# rapidshark-dart-detector-backlight-mk-2_.net
KiCad netlist of a schematic drawn in EAGLE
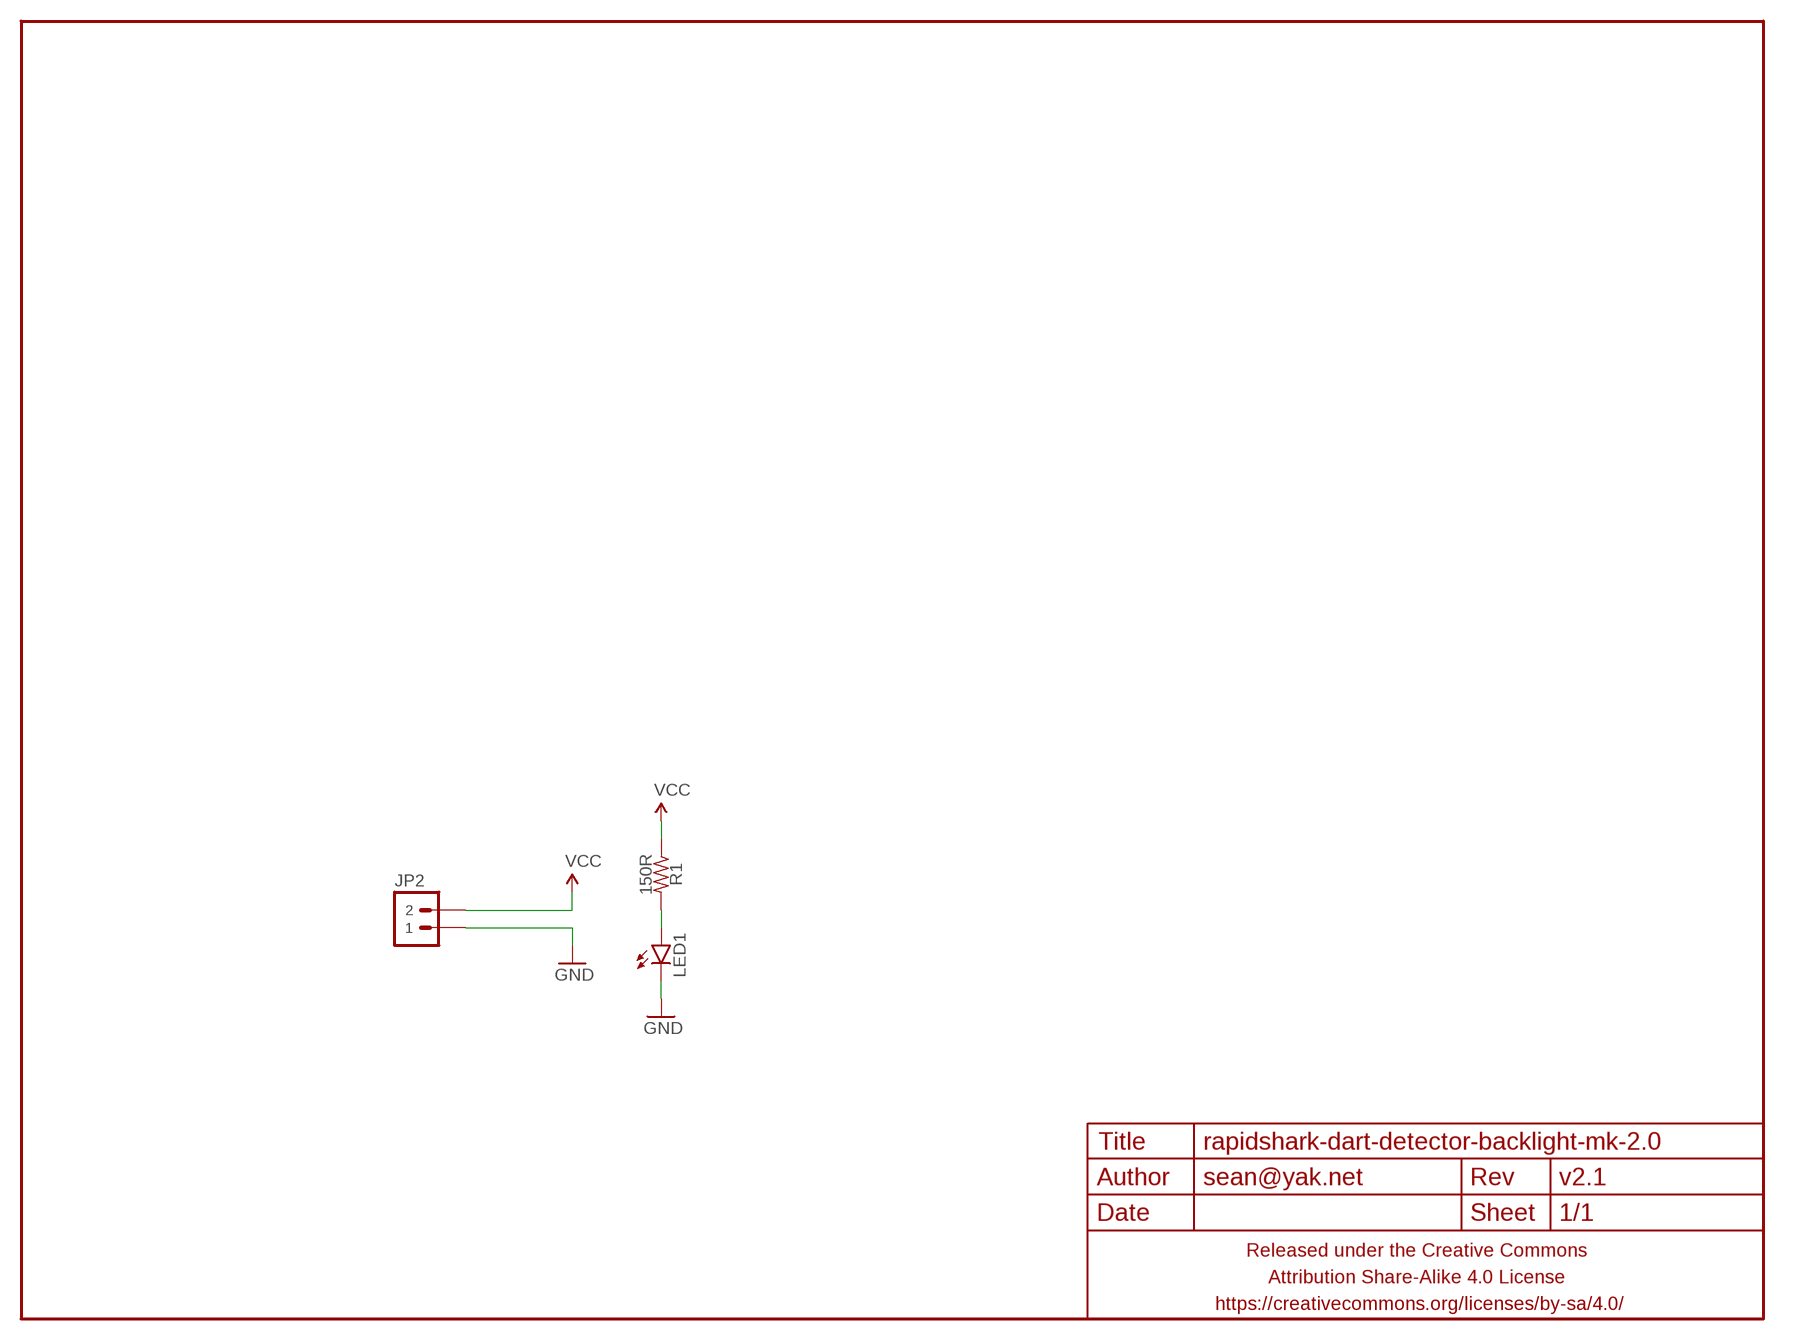
[diagram p0: schematic, sheet 1]

(export (version "E")
  (design (tool "Eeschema 10.0.6"))
  (components
    (comp (ref "FRAME1")
      (value "FRAME-LETTERNO_PACKAGE")
      (footprint "eagle-import:DUMMY")
      (fields (field (name "DESIGNER") "sean@yak.net") (field (name "VERSION") "v2.1"))
      (libsource (lib "eagle-import") (part "FRAME-LETTERNO_PACKAGE"))
    )
    (comp (ref "JP2")
      (value "M02JST-PTH-RA-R+")
      (footprint "eagle-import:JST-2-PH-RA-PTH-R+")
      (libsource (lib "eagle-import") (part "M02JST-PTH-RA-R+"))
    )
    (comp (ref "LED1")
      (value "LED5MM_SHORTPADS")
      (footprint "eagle-import:LED5MM_SHORTPADS")
      (libsource (lib "eagle-import") (part "LED5MM_SHORTPADS"))
    )
    (comp (ref "R1")
      (value "150R")
      (footprint "eagle-import:RESISTOR-AXIAL-PTH-6.35MM")
      (libsource (lib "eagle-import") (part "RESISTORPTH-AXIAL-6.35MM"))
    )
  )
  (nets
    (net (code "1") (name "GND") (class "Default")
      (node (ref "JP2") (pin "1") (pinfunction "1_1") (pintype "passive"))
      (node (ref "LED1") (pin "K") (pinfunction "C_K") (pintype "passive"))
    )
    (net (code "2") (name "Net-(R1-2)") (class "Default")
      (node (ref "LED1") (pin "A") (pinfunction "A_A") (pintype "passive"))
      (node (ref "R1") (pin "P$2") (pinfunction "2_P$2") (pintype "passive"))
    )
    (net (code "3") (name "VCC") (class "Default")
      (node (ref "JP2") (pin "2") (pinfunction "2_2") (pintype "passive"))
      (node (ref "R1") (pin "P$1") (pinfunction "1_P$1") (pintype "passive"))
    )
  )
)
